# OSD.net
KiCad netlist of a schematic drawn in Altium Designer
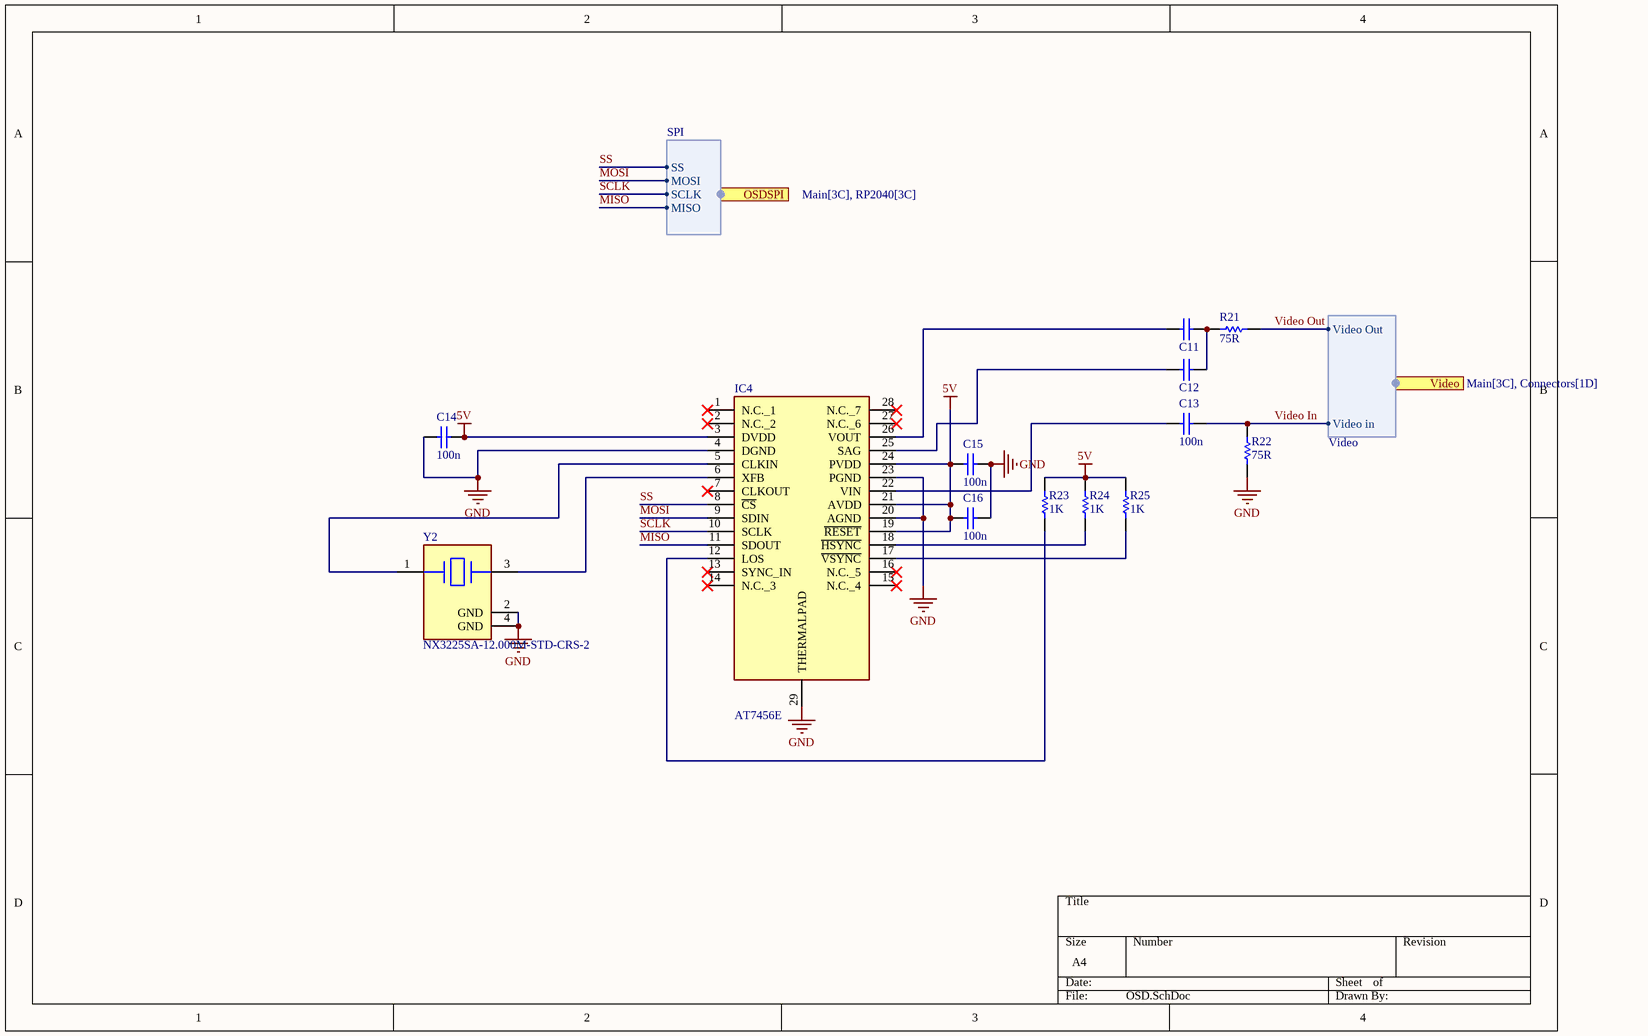
[diagram p0: OSD.SchDoc]

(export (version "E")
  (design (tool "Eeschema 10.0.6"))
  (components
    (comp (ref "C11")
      (value "10µF")
      (footprint "WCAP-CSGP_0603_L1.6W0.8H0.8_Reflow")
      (description "WCAP-CSGP Multilayer Ceramic Chip Capacitor, General Purpose, size 0603, X5R, 10µF, 25VDC")
      (fields
        (field (name "MANUFACTURER PART NUMBER") "885012106031")
        (field (name "MANUFACTURER") "Wurth Elektronik")
      )
      (libsource (lib "Altium_WCAP-CSGP (rev22e)") (part "885012106031"))
    )
    (comp (ref "C12")
      (value "10µF")
      (footprint "WCAP-CSGP_0603_L1.6W0.8H0.8_Reflow")
      (description "WCAP-CSGP Multilayer Ceramic Chip Capacitor, General Purpose, size 0603, X5R, 10µF, 25VDC")
      (fields
        (field (name "MANUFACTURER PART NUMBER") "885012106031")
        (field (name "MANUFACTURER") "Wurth Elektronik")
      )
      (libsource (lib "Altium_WCAP-CSGP (rev22e)") (part "885012106031"))
    )
    (comp (ref "C13")
      (value "100n")
      (footprint "CAPC0603(1608)55_N")
      (description "Keramikvielschichtkondensator, SMD, Baureihe MC, ± 20%")
      (fields (field (name "MANUFACTURER") "Multicomp"))
      (libsource (lib "Standardbauteile") (part "Cap 100n"))
    )
    (comp (ref "C14")
      (value "100n")
      (footprint "CAPC0603(1608)55_N")
      (description "Keramikvielschichtkondensator, SMD, Baureihe MC, ± 20%")
      (fields (field (name "MANUFACTURER") "Multicomp"))
      (libsource (lib "Standardbauteile") (part "Cap 100n"))
    )
    (comp (ref "C15")
      (value "100n")
      (footprint "CAPC0603(1608)55_N")
      (description "Keramikvielschichtkondensator, SMD, Baureihe MC, ± 20%")
      (fields (field (name "MANUFACTURER") "Multicomp"))
      (libsource (lib "Standardbauteile") (part "Cap 100n"))
    )
    (comp (ref "C16")
      (value "100n")
      (footprint "CAPC0603(1608)55_N")
      (description "Keramikvielschichtkondensator, SMD, Baureihe MC, ± 20%")
      (fields (field (name "MANUFACTURER") "Multicomp"))
      (libsource (lib "Standardbauteile") (part "Cap 100n"))
    )
    (comp (ref "IC4")
      (value "AT7456E")
      (footprint "Custom Components:SOP65P640X120-29N")
      (description "Integrated Circuit")
      (libsource (lib "*") (part "AT7456E"))
    )
    (comp (ref "R21")
      (value "75R")
      (footprint "RESC0603(1608)_N")
      (description "Chipwiderstand, SMD, Baureihe MC, 1%")
      (fields (field (name "MANUFACTURER") "Multicomp"))
      (libsource (lib "Standardbauteile") (part "Res 750R"))
    )
    (comp (ref "R22")
      (value "75R")
      (footprint "RESC0603(1608)_N")
      (description "Chipwiderstand, SMD, Baureihe MC, 1%")
      (fields (field (name "MANUFACTURER") "Multicomp"))
      (libsource (lib "Standardbauteile") (part "Res 750R"))
    )
    (comp (ref "R23")
      (value "1K")
      (footprint "RESC0603(1608)_N")
      (description "Chipwiderstand, SMD, Baureihe MC, 1%")
      (fields (field (name "MANUFACTURER") "Multicomp"))
      (libsource (lib "Standardbauteile") (part "Res 1K"))
    )
    (comp (ref "R24")
      (value "1K")
      (footprint "RESC0603(1608)_N")
      (description "Chipwiderstand, SMD, Baureihe MC, 1%")
      (fields (field (name "MANUFACTURER") "Multicomp"))
      (libsource (lib "Standardbauteile") (part "Res 1K"))
    )
    (comp (ref "R25")
      (value "1K")
      (footprint "RESC0603(1608)_N")
      (description "Chipwiderstand, SMD, Baureihe MC, 1%")
      (fields (field (name "MANUFACTURER") "Multicomp"))
      (libsource (lib "Standardbauteile") (part "Res 1K"))
    )
    (comp (ref "Y2")
      (value "NX3225SA-12.000M-STD-CRS-2")
      (footprint "FP-NX3225SA-MFG")
      (libsource (lib "Altium Content Vault") (part "48e526d86b7f2615d98721063c72f49"))
    )
  )
  (nets
    (net (code "3") (name "/MISO") (class "Default")
      (node (ref "IC4") (pin "11") (pinfunction "SDOUT_11") (pintype "passive"))
    )
    (net (code "4") (name "/MOSI") (class "Default")
      (node (ref "IC4") (pin "9") (pinfunction "SDIN_9") (pintype "passive"))
    )
    (net (code "5") (name "/SCLK") (class "Default")
      (node (ref "IC4") (pin "10") (pinfunction "SCLK_10") (pintype "passive"))
    )
    (net (code "6") (name "/SS") (class "Default")
      (node (ref "IC4") (pin "8") (pinfunction "~{CS}_8") (pintype "passive"))
    )
    (net (code "7") (name "/Video In") (class "Default")
      (node (ref "C13") (pin "2") (pinfunction "2_2") (pintype "passive"))
      (node (ref "R22") (pin "2") (pinfunction "2_2") (pintype "passive"))
    )
    (net (code "8") (name "/Video Out") (class "Default")
      (node (ref "R21") (pin "1") (pinfunction "1_1") (pintype "passive"))
    )
    (net (code "11") (name "5V") (class "Default")
      (node (ref "C14") (pin "2") (pinfunction "2_2") (pintype "passive"))
      (node (ref "C15") (pin "1") (pinfunction "1_1") (pintype "passive"))
      (node (ref "C16") (pin "1") (pinfunction "1_1") (pintype "passive"))
      (node (ref "IC4") (pin "19") (pinfunction "~{RESET}_19") (pintype "passive"))
      (node (ref "IC4") (pin "21") (pinfunction "AVDD_21") (pintype "passive"))
      (node (ref "IC4") (pin "24") (pinfunction "PVDD_24") (pintype "passive"))
      (node (ref "IC4") (pin "3") (pinfunction "DVDD_3") (pintype "passive"))
      (node (ref "R23") (pin "2") (pinfunction "2_2") (pintype "passive"))
      (node (ref "R24") (pin "2") (pinfunction "2_2") (pintype "passive"))
      (node (ref "R25") (pin "2") (pinfunction "2_2") (pintype "passive"))
    )
    (net (code "12") (name "GND") (class "Default")
      (node (ref "C14") (pin "1") (pinfunction "1_1") (pintype "passive"))
      (node (ref "C15") (pin "2") (pinfunction "2_2") (pintype "passive"))
      (node (ref "C16") (pin "2") (pinfunction "2_2") (pintype "passive"))
      (node (ref "IC4") (pin "20") (pinfunction "AGND_20") (pintype "passive"))
      (node (ref "IC4") (pin "23") (pinfunction "PGND_23") (pintype "passive"))
      (node (ref "IC4") (pin "29") (pinfunction "THERMALPAD_29") (pintype "passive"))
      (node (ref "IC4") (pin "4") (pinfunction "DGND_4") (pintype "passive"))
      (node (ref "R22") (pin "1") (pinfunction "1_1") (pintype "passive"))
      (node (ref "Y2") (pin "2") (pinfunction "GND_2") (pintype "power_in"))
      (node (ref "Y2") (pin "4") (pinfunction "GND_4") (pintype "power_in"))
    )
    (net (code "13") (name "Net-(C11-Pad2)") (class "Default")
      (node (ref "C11") (pin "2") (pinfunction "2_2") (pintype "passive"))
      (node (ref "C12") (pin "2") (pinfunction "2_2") (pintype "passive"))
      (node (ref "R21") (pin "2") (pinfunction "2_2") (pintype "passive"))
    )
    (net (code "14") (name "Net-(IC4-CLKIN)") (class "Default")
      (node (ref "IC4") (pin "5") (pinfunction "CLKIN_5") (pintype "passive"))
      (node (ref "Y2") (pin "1") (pinfunction "1_1") (pintype "passive"))
    )
    (net (code "15") (name "Net-(IC4-LOS)") (class "Default")
      (node (ref "IC4") (pin "12") (pinfunction "LOS_12") (pintype "passive"))
      (node (ref "R23") (pin "1") (pinfunction "1_1") (pintype "passive"))
    )
    (net (code "16") (name "Net-(IC4-SAG)") (class "Default")
      (node (ref "C12") (pin "1") (pinfunction "1_1") (pintype "passive"))
      (node (ref "IC4") (pin "25") (pinfunction "SAG_25") (pintype "passive"))
    )
    (net (code "17") (name "Net-(IC4-VIN)") (class "Default")
      (node (ref "C13") (pin "1") (pinfunction "1_1") (pintype "passive"))
      (node (ref "IC4") (pin "22") (pinfunction "VIN_22") (pintype "passive"))
    )
    (net (code "18") (name "Net-(IC4-VOUT)") (class "Default")
      (node (ref "C11") (pin "1") (pinfunction "1_1") (pintype "passive"))
      (node (ref "IC4") (pin "26") (pinfunction "VOUT_26") (pintype "passive"))
    )
    (net (code "19") (name "Net-(IC4-XFB)") (class "Default")
      (node (ref "IC4") (pin "6") (pinfunction "XFB_6") (pintype "passive"))
      (node (ref "Y2") (pin "3") (pinfunction "3_3") (pintype "passive"))
    )
    (net (code "20") (name "Net-(IC4-~{HSYNC})") (class "Default")
      (node (ref "IC4") (pin "18") (pinfunction "~{HSYNC}_18") (pintype "passive"))
      (node (ref "R24") (pin "1") (pinfunction "1_1") (pintype "passive"))
    )
    (net (code "21") (name "Net-(IC4-~{VSYNC})") (class "Default")
      (node (ref "IC4") (pin "17") (pinfunction "~{VSYNC}_17") (pintype "passive"))
      (node (ref "R25") (pin "1") (pinfunction "1_1") (pintype "passive"))
    )
    (net (code "22") (name "unconnected-(IC4-CLKOUT-Pad7)") (class "Default")
      (node (ref "IC4") (pin "7") (pinfunction "CLKOUT_7") (pintype "passive+no_connect"))
    )
    (net (code "23") (name "unconnected-(IC4-N.C._1-Pad1)") (class "Default")
      (node (ref "IC4") (pin "1") (pinfunction "N.C._1_1") (pintype "passive+no_connect"))
    )
    (net (code "24") (name "unconnected-(IC4-N.C._2-Pad2)") (class "Default")
      (node (ref "IC4") (pin "2") (pinfunction "N.C._2_2") (pintype "passive+no_connect"))
    )
    (net (code "25") (name "unconnected-(IC4-N.C._3-Pad14)") (class "Default")
      (node (ref "IC4") (pin "14") (pinfunction "N.C._3_14") (pintype "passive+no_connect"))
    )
    (net (code "26") (name "unconnected-(IC4-N.C._4-Pad15)") (class "Default")
      (node (ref "IC4") (pin "15") (pinfunction "N.C._4_15") (pintype "passive+no_connect"))
    )
    (net (code "27") (name "unconnected-(IC4-N.C._5-Pad16)") (class "Default")
      (node (ref "IC4") (pin "16") (pinfunction "N.C._5_16") (pintype "passive+no_connect"))
    )
    (net (code "28") (name "unconnected-(IC4-N.C._6-Pad27)") (class "Default")
      (node (ref "IC4") (pin "27") (pinfunction "N.C._6_27") (pintype "passive+no_connect"))
    )
    (net (code "29") (name "unconnected-(IC4-N.C._7-Pad28)") (class "Default")
      (node (ref "IC4") (pin "28") (pinfunction "N.C._7_28") (pintype "passive+no_connect"))
    )
    (net (code "30") (name "unconnected-(IC4-SYNC_IN-Pad13)") (class "Default")
      (node (ref "IC4") (pin "13") (pinfunction "SYNC_IN_13") (pintype "passive+no_connect"))
    )
  )
)
